# DM1098OAKW_IMX378.net
KiCad netlist of a schematic drawn in Altium Designer
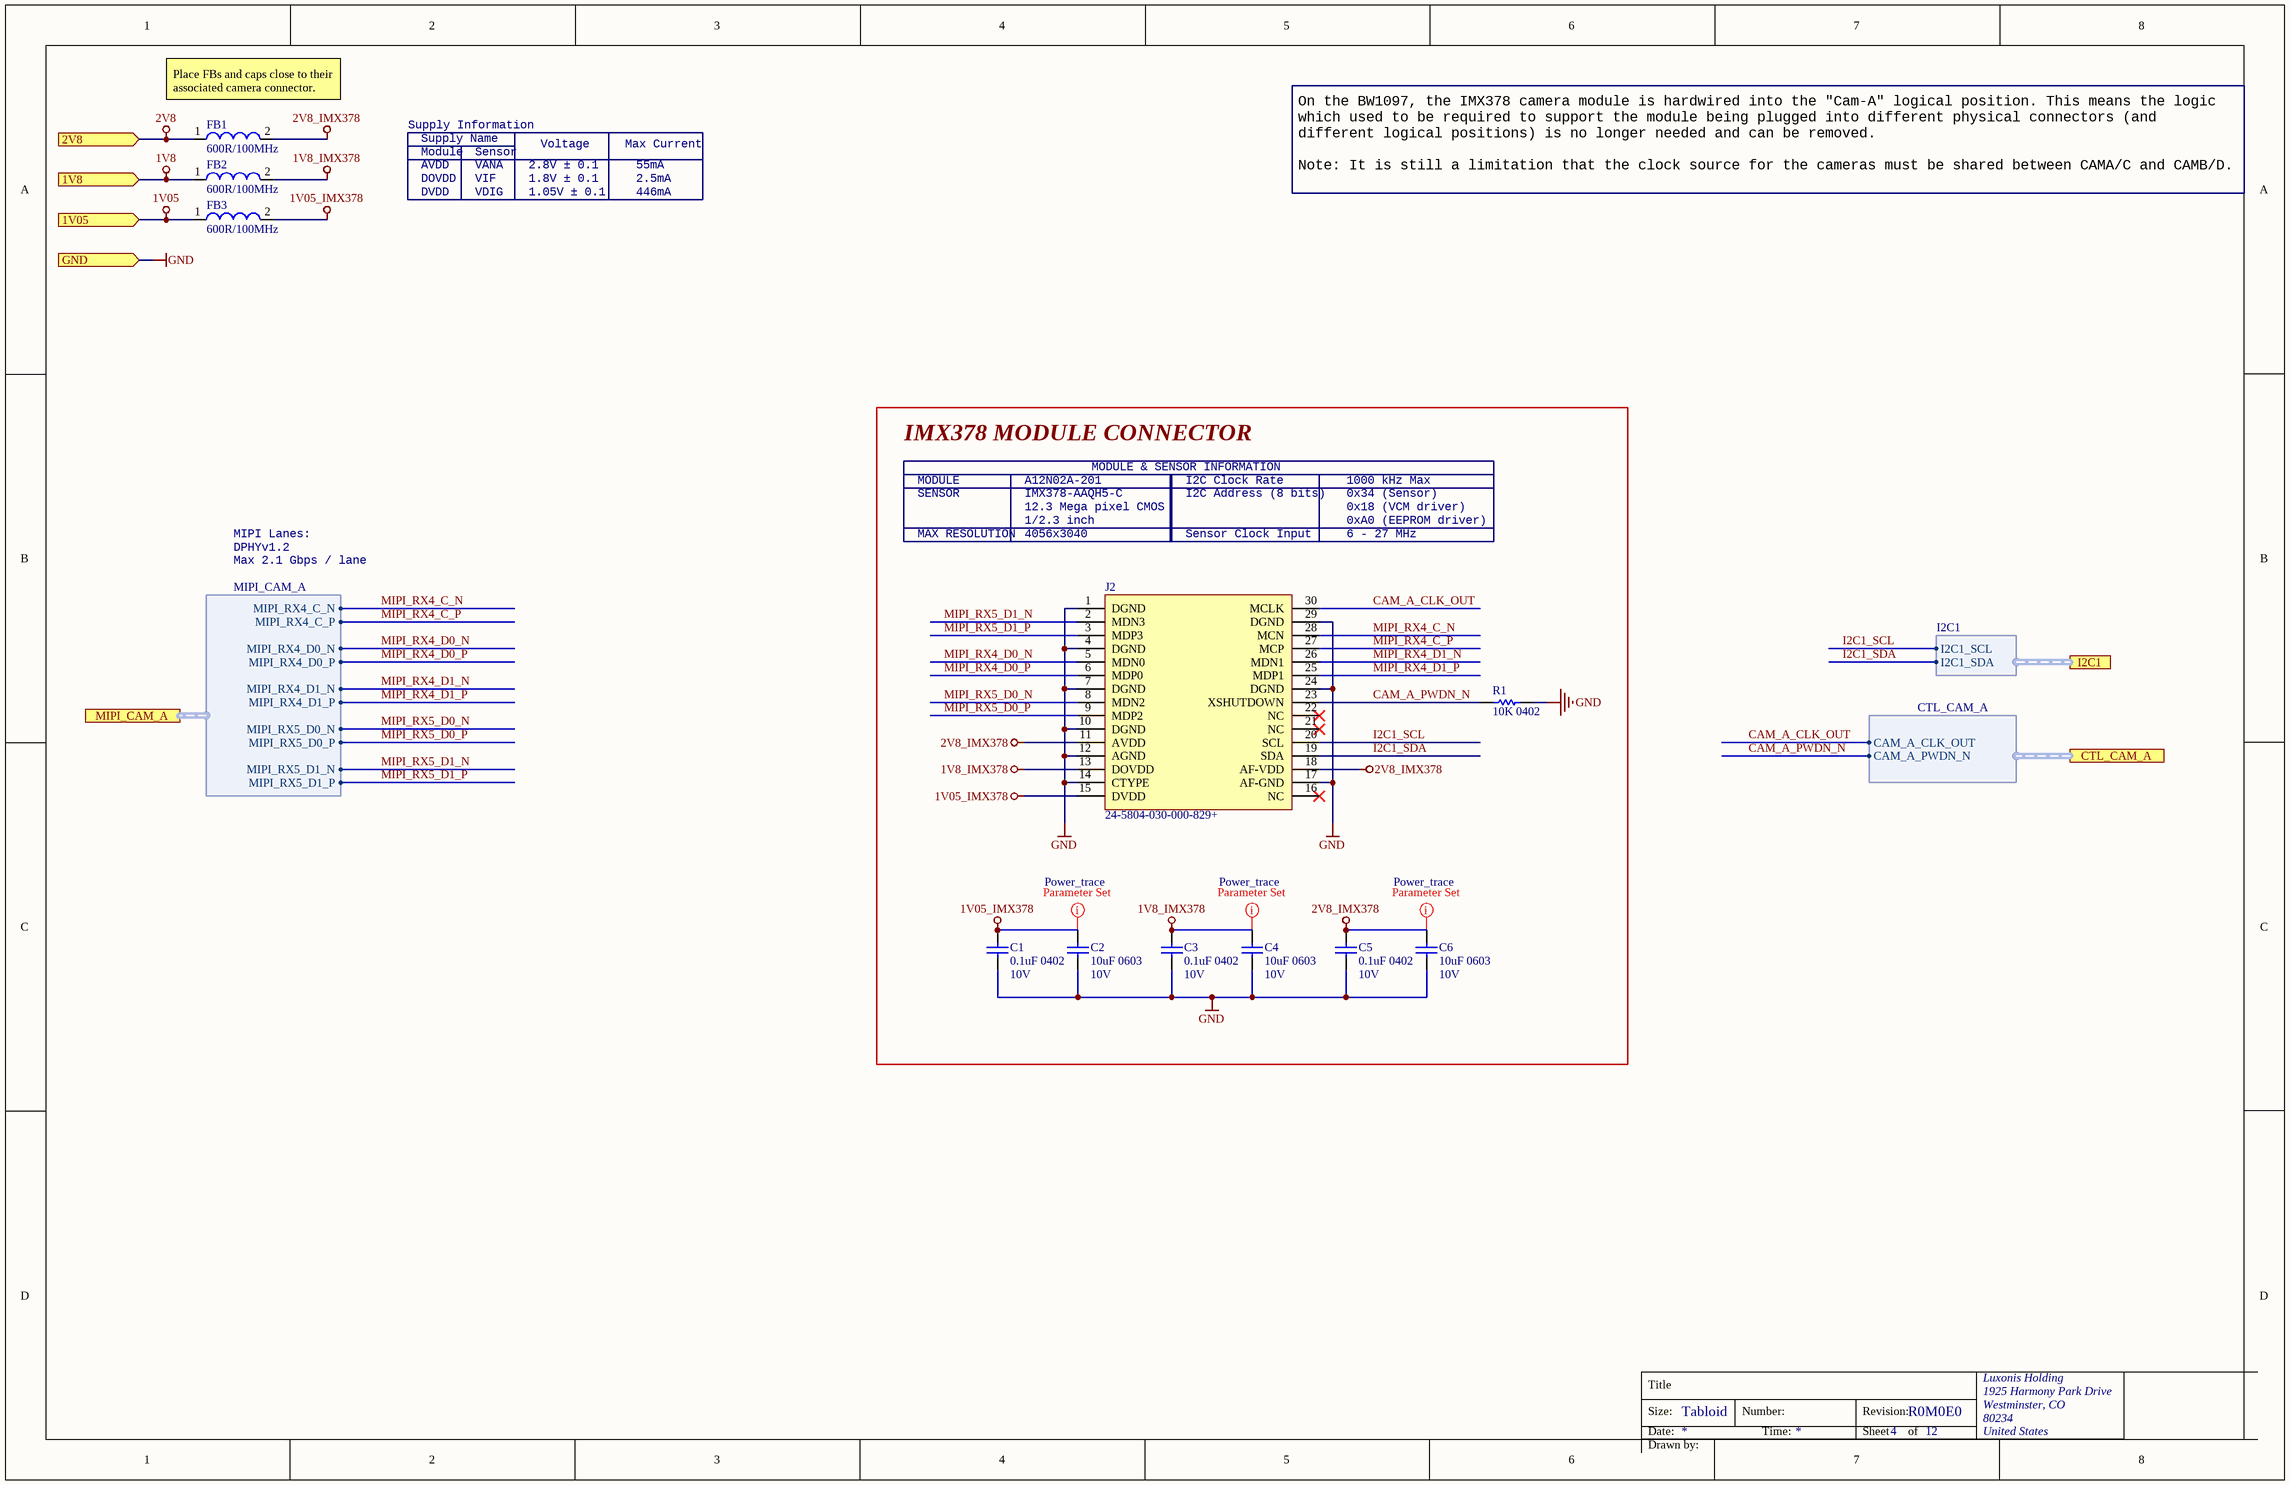
[diagram p0: DM1098OAKW_IMX378.SchDoc]

(export (version "E")
  (design (tool "Eeschema 10.0.6"))
  (components
    (comp (ref "C1")
      (value "0.1uF 0402")
      (footprint "CAP_Altium_Vault_Generic:CAPC0402(1005)70_L")
      (description "CAP CER 0.1UF 10V X7R 0402 5%")
      (fields (field (name "TOLERANCE") "5%") (field (name "VOLTAGE RATING") "10V"))
      (libsource (lib "LuxonisMaster") (part "GRM155R71A104JA01D"))
    )
    (comp (ref "C2")
      (value "10uF 0603")
      (footprint "CAP_Altium_Vault_Generic:CAPC0603(1608)100_L")
      (description "CAP CER 10UF 10V X5R 0603 20%")
      (fields (field (name "TOLERANCE") "20%") (field (name "VOLTAGE RATING") "10V"))
      (libsource (lib "LuxonisMaster") (part "GRM188R61A106ME69D"))
    )
    (comp (ref "C3")
      (value "0.1uF 0402")
      (footprint "CAP_Altium_Vault_Generic:CAPC0402(1005)70_L")
      (description "CAP CER 0.1UF 10V X7R 0402 5%")
      (fields (field (name "TOLERANCE") "5%") (field (name "VOLTAGE RATING") "10V"))
      (libsource (lib "LuxonisMaster") (part "GRM155R71A104JA01D"))
    )
    (comp (ref "C4")
      (value "10uF 0603")
      (footprint "CAP_Altium_Vault_Generic:CAPC0603(1608)100_L")
      (description "CAP CER 10UF 10V X5R 0603 20%")
      (fields (field (name "TOLERANCE") "20%") (field (name "VOLTAGE RATING") "10V"))
      (libsource (lib "LuxonisMaster") (part "GRM188R61A106ME69D"))
    )
    (comp (ref "C5")
      (value "0.1uF 0402")
      (footprint "CAP_Altium_Vault_Generic:CAPC0402(1005)70_L")
      (description "CAP CER 0.1UF 10V X7R 0402 5%")
      (fields (field (name "TOLERANCE") "5%") (field (name "VOLTAGE RATING") "10V"))
      (libsource (lib "LuxonisMaster") (part "GRM155R71A104JA01D"))
    )
    (comp (ref "C6")
      (value "10uF 0603")
      (footprint "CAP_Altium_Vault_Generic:CAPC0603(1608)100_L")
      (description "CAP CER 10UF 10V X5R 0603 20%")
      (fields (field (name "TOLERANCE") "20%") (field (name "VOLTAGE RATING") "10V"))
      (libsource (lib "LuxonisMaster") (part "GRM188R61A106ME69D"))
    )
    (comp (ref "FB1")
      (value "600R/100MHz")
      (footprint "LuxonisMaster:2508056017Y2")
      (description "FERRITE BEAD, 0.1OHM, 2A, 0805, 600R/100MHz")
      (fields (field (name "TOLERANCE") "25%"))
      (libsource (lib "LuxonisMaster") (part "2508056017Y2"))
    )
    (comp (ref "FB2")
      (value "600R/100MHz")
      (footprint "LuxonisMaster:2508056017Y2")
      (description "FERRITE BEAD, 0.1OHM, 2A, 0805, 600R/100MHz")
      (fields (field (name "TOLERANCE") "25%"))
      (libsource (lib "LuxonisMaster") (part "2508056017Y2"))
    )
    (comp (ref "FB3")
      (value "600R/100MHz")
      (footprint "LuxonisMaster:2508056017Y2")
      (description "FERRITE BEAD, 0.1OHM, 2A, 0805, 600R/100MHz")
      (fields (field (name "TOLERANCE") "25%"))
      (libsource (lib "LuxonisMaster") (part "2508056017Y2"))
    )
    (comp (ref "J2")
      (value "24-5804-030-000-829+")
      (footprint "DM1092_R0M0E0:A12N02A-201_1.6mmbrd_MatedModule")
      (description "CONN Series 5804 board to board 0.4mm pitch 30 way connector")
      (libsource (lib "DM1092_R0M0E0") (part "A12N02A-201_Connector_(1.6mm_brd)"))
    )
    (comp (ref "R1")
      (value "10K 0402")
      (footprint "RES_Altium_Vault_Generic:RESC0402(1005)_L")
      (fields (field (name "TOLERANCE") "1%"))
      (libsource (lib "LuxonisMaster") (part "RC0402FR-1310KL"))
    )
  )
  (nets
    (net (code "4") (name "/CAM_A_CLK_OUT") (class "Default")
      (node (ref "J2") (pin "30") (pinfunction "MCLK_30") (pintype "passive"))
    )
    (net (code "5") (name "/CAM_A_PWDN_N") (class "Default")
      (node (ref "J2") (pin "23") (pinfunction "XSHUTDOWN_23") (pintype "passive"))
      (node (ref "R1") (pin "1") (pinfunction "1_1") (pintype "passive"))
    )
    (net (code "6") (name "/I2C1_SCL") (class "Default")
      (node (ref "J2") (pin "20") (pinfunction "SCL_20") (pintype "passive"))
    )
    (net (code "7") (name "/I2C1_SDA") (class "Default")
      (node (ref "J2") (pin "19") (pinfunction "SDA_19") (pintype "passive"))
    )
    (net (code "8") (name "/MIPI_RX4_C_N") (class "Default")
      (node (ref "J2") (pin "28") (pinfunction "MCN_28") (pintype "passive"))
    )
    (net (code "9") (name "/MIPI_RX4_C_P") (class "Default")
      (node (ref "J2") (pin "27") (pinfunction "MCP_27") (pintype "passive"))
    )
    (net (code "10") (name "/MIPI_RX4_D0_N") (class "Default")
      (node (ref "J2") (pin "5") (pinfunction "MDN0_5") (pintype "passive"))
    )
    (net (code "11") (name "/MIPI_RX4_D0_P") (class "Default")
      (node (ref "J2") (pin "6") (pinfunction "MDP0_6") (pintype "passive"))
    )
    (net (code "12") (name "/MIPI_RX4_D1_N") (class "Default")
      (node (ref "J2") (pin "26") (pinfunction "MDN1_26") (pintype "passive"))
    )
    (net (code "13") (name "/MIPI_RX4_D1_P") (class "Default")
      (node (ref "J2") (pin "25") (pinfunction "MDP1_25") (pintype "passive"))
    )
    (net (code "14") (name "/MIPI_RX5_D0_N") (class "Default")
      (node (ref "J2") (pin "8") (pinfunction "MDN2_8") (pintype "passive"))
    )
    (net (code "15") (name "/MIPI_RX5_D0_P") (class "Default")
      (node (ref "J2") (pin "9") (pinfunction "MDP2_9") (pintype "passive"))
    )
    (net (code "16") (name "/MIPI_RX5_D1_N") (class "Default")
      (node (ref "J2") (pin "2") (pinfunction "MDN3_2") (pintype "passive"))
    )
    (net (code "17") (name "/MIPI_RX5_D1_P") (class "Default")
      (node (ref "J2") (pin "3") (pinfunction "MDP3_3") (pintype "passive"))
    )
    (net (code "21") (name "1V05") (class "Default")
      (node (ref "FB3") (pin "1") (pinfunction "1_1") (pintype "passive"))
    )
    (net (code "22") (name "1V05_IMX378") (class "Default")
      (node (ref "C1") (pin "2") (pinfunction "2_2") (pintype "passive"))
      (node (ref "C2") (pin "2") (pinfunction "2_2") (pintype "passive"))
      (node (ref "FB3") (pin "2") (pinfunction "2_2") (pintype "passive"))
      (node (ref "J2") (pin "15") (pinfunction "DVDD_15") (pintype "passive"))
    )
    (net (code "23") (name "1V8") (class "Default")
      (node (ref "FB2") (pin "1") (pinfunction "1_1") (pintype "passive"))
    )
    (net (code "24") (name "1V8_IMX378") (class "Default")
      (node (ref "C3") (pin "2") (pinfunction "2_2") (pintype "passive"))
      (node (ref "C4") (pin "2") (pinfunction "2_2") (pintype "passive"))
      (node (ref "FB2") (pin "2") (pinfunction "2_2") (pintype "passive"))
      (node (ref "J2") (pin "13") (pinfunction "DOVDD_13") (pintype "passive"))
    )
    (net (code "25") (name "2V8") (class "Default")
      (node (ref "FB1") (pin "1") (pinfunction "1_1") (pintype "passive"))
    )
    (net (code "26") (name "2V8_IMX378") (class "Default")
      (node (ref "C5") (pin "2") (pinfunction "2_2") (pintype "passive"))
      (node (ref "C6") (pin "2") (pinfunction "2_2") (pintype "passive"))
      (node (ref "FB1") (pin "2") (pinfunction "2_2") (pintype "passive"))
      (node (ref "J2") (pin "11") (pinfunction "AVDD_11") (pintype "passive"))
      (node (ref "J2") (pin "18") (pinfunction "AF-VDD_18") (pintype "passive"))
    )
    (net (code "27") (name "GND") (class "Default")
      (node (ref "C1") (pin "1") (pinfunction "1_1") (pintype "passive"))
      (node (ref "C2") (pin "1") (pinfunction "1_1") (pintype "passive"))
      (node (ref "C3") (pin "1") (pinfunction "1_1") (pintype "passive"))
      (node (ref "C4") (pin "1") (pinfunction "1_1") (pintype "passive"))
      (node (ref "C5") (pin "1") (pinfunction "1_1") (pintype "passive"))
      (node (ref "C6") (pin "1") (pinfunction "1_1") (pintype "passive"))
      (node (ref "J2") (pin "1") (pinfunction "DGND_1") (pintype "passive"))
      (node (ref "J2") (pin "10") (pinfunction "DGND_10") (pintype "passive"))
      (node (ref "J2") (pin "12") (pinfunction "AGND_12") (pintype "passive"))
      (node (ref "J2") (pin "14") (pinfunction "CTYPE_14") (pintype "passive"))
      (node (ref "J2") (pin "17") (pinfunction "AF-GND_17") (pintype "passive"))
      (node (ref "J2") (pin "24") (pinfunction "DGND_24") (pintype "passive"))
      (node (ref "J2") (pin "29") (pinfunction "DGND_29") (pintype "passive"))
      (node (ref "J2") (pin "4") (pinfunction "DGND_4") (pintype "passive"))
      (node (ref "J2") (pin "7") (pinfunction "DGND_7") (pintype "passive"))
      (node (ref "R1") (pin "2") (pinfunction "2_2") (pintype "passive"))
    )
    (net (code "28") (name "unconnected-(J2-NC-Pad16)") (class "Default")
      (node (ref "J2") (pin "16") (pinfunction "NC_16") (pintype "passive+no_connect"))
    )
    (net (code "29") (name "unconnected-(J2-NC-Pad21)") (class "Default")
      (node (ref "J2") (pin "21") (pinfunction "NC_21") (pintype "passive+no_connect"))
    )
    (net (code "30") (name "unconnected-(J2-NC-Pad22)") (class "Default")
      (node (ref "J2") (pin "22") (pinfunction "NC_22") (pintype "passive+no_connect"))
    )
  )
)
